# SCH_POWER_5V_to_3_3V.net
KiCad netlist of a schematic drawn in Altium Designer
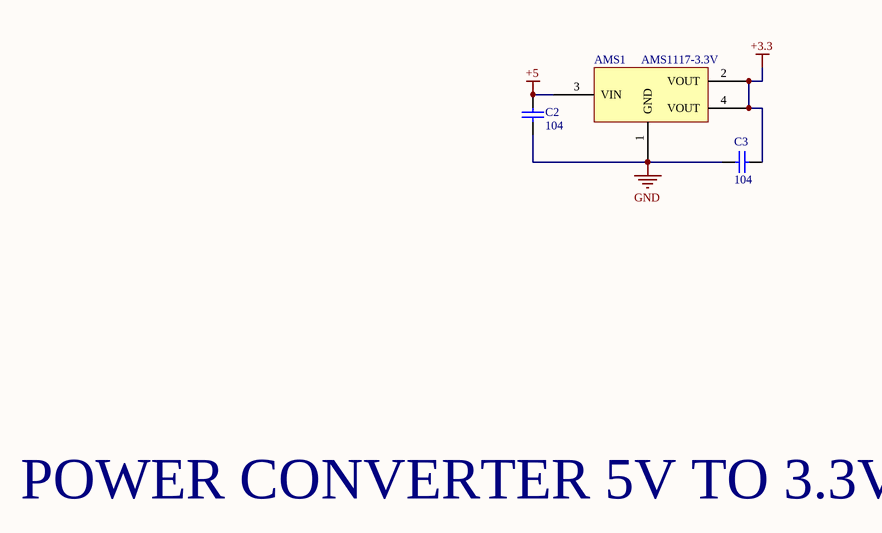
[diagram p0: SCH_POWER_5V_to_3.3V.SchDoc]

(export (version "E")
  (design (tool "Eeschema 10.0.6"))
  (components
    (comp (ref "AMS1")
      (value "AMS1117-3.3V")
      (footprint "SOT223")
      (description "Dán")
      (libsource (lib "Altium_Lib_by_KhueNguyenCreator") (part "AMS1117 SMD"))
    )
    (comp (ref "C2")
      (value "104")
      (footprint "tu 0603")
      (description "Dán")
      (libsource (lib "Altium_Lib_by_KhueNguyenCreator") (part "Tu 0603 106 16V 20%"))
    )
    (comp (ref "C3")
      (value "104")
      (footprint "tu 0603")
      (description "Dán")
      (libsource (lib "Altium_Lib_by_KhueNguyenCreator") (part "Tu 0603 106 16V 20%"))
    )
  )
  (nets
    (net (code "1") (name "+3.3") (class "Default")
      (node (ref "AMS1") (pin "2") (pinfunction "VOUT_2") (pintype "passive"))
      (node (ref "AMS1") (pin "4") (pinfunction "VOUT_4") (pintype "passive"))
      (node (ref "C3") (pin "2") (pinfunction "2_2") (pintype "passive"))
    )
    (net (code "2") (name "+5") (class "Default")
      (node (ref "AMS1") (pin "3") (pinfunction "VIN_3") (pintype "passive"))
      (node (ref "C2") (pin "2") (pinfunction "2_2") (pintype "passive"))
    )
    (net (code "3") (name "GND") (class "Default")
      (node (ref "AMS1") (pin "1") (pinfunction "GND_1") (pintype "passive"))
      (node (ref "C2") (pin "1") (pinfunction "1_1") (pintype "passive"))
      (node (ref "C3") (pin "1") (pinfunction "1_1") (pintype "passive"))
    )
  )
)
